# SlaveMCU.net
KiCad netlist of a schematic drawn in EAGLE
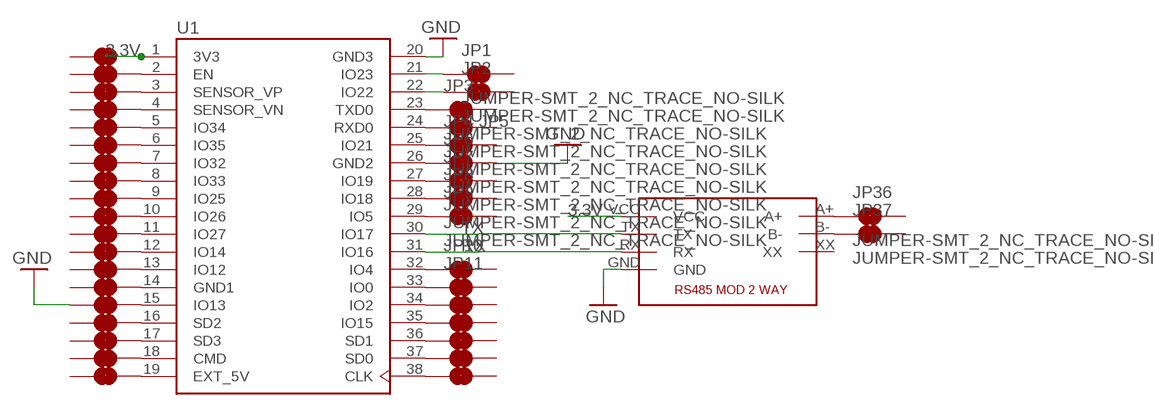
[diagram p0: schematic, sheet 1]

(export (version "E")
  (design (tool "Eeschema 10.0.6"))
  (components
    (comp (ref "JP1")
      (value "JUMPER-SMT_2_NC_TRACE_NO-SILK")
      (footprint "eagle-import:SMT-JUMPER_2_NC_TRACE_NO-SILK")
      (libsource (lib "eagle-import") (part "JUMPER-SMT_2_NC_TRACE_NO-SILK"))
    )
    (comp (ref "JP2")
      (value "JUMPER-SMT_2_NC_TRACE_NO-SILK")
      (footprint "eagle-import:SMT-JUMPER_2_NC_TRACE_NO-SILK")
      (libsource (lib "eagle-import") (part "JUMPER-SMT_2_NC_TRACE_NO-SILK"))
    )
    (comp (ref "JP3")
      (value "JUMPER-SMT_2_NC_TRACE_NO-SILK")
      (footprint "eagle-import:SMT-JUMPER_2_NC_TRACE_NO-SILK")
      (libsource (lib "eagle-import") (part "JUMPER-SMT_2_NC_TRACE_NO-SILK"))
    )
    (comp (ref "JP4")
      (value "JUMPER-SMT_2_NC_TRACE_NO-SILK")
      (footprint "eagle-import:SMT-JUMPER_2_NC_TRACE_NO-SILK")
      (libsource (lib "eagle-import") (part "JUMPER-SMT_2_NC_TRACE_NO-SILK"))
    )
    (comp (ref "JP5")
      (value "JUMPER-SMT_2_NC_TRACE_NO-SILK")
      (footprint "eagle-import:SMT-JUMPER_2_NC_TRACE_NO-SILK")
      (libsource (lib "eagle-import") (part "JUMPER-SMT_2_NC_TRACE_NO-SILK"))
    )
    (comp (ref "JP6")
      (value "JUMPER-SMT_2_NC_TRACE_NO-SILK")
      (footprint "eagle-import:SMT-JUMPER_2_NC_TRACE_NO-SILK")
      (libsource (lib "eagle-import") (part "JUMPER-SMT_2_NC_TRACE_NO-SILK"))
    )
    (comp (ref "JP7")
      (value "JUMPER-SMT_2_NC_TRACE_NO-SILK")
      (footprint "eagle-import:SMT-JUMPER_2_NC_TRACE_NO-SILK")
      (libsource (lib "eagle-import") (part "JUMPER-SMT_2_NC_TRACE_NO-SILK"))
    )
    (comp (ref "JP8")
      (value "JUMPER-SMT_2_NC_TRACE_NO-SILK")
      (footprint "eagle-import:SMT-JUMPER_2_NC_TRACE_NO-SILK")
      (libsource (lib "eagle-import") (part "JUMPER-SMT_2_NC_TRACE_NO-SILK"))
    )
    (comp (ref "JP9")
      (value "JUMPER-SMT_2_NC_TRACE_NO-SILK")
      (footprint "eagle-import:SMT-JUMPER_2_NC_TRACE_NO-SILK")
      (libsource (lib "eagle-import") (part "JUMPER-SMT_2_NC_TRACE_NO-SILK"))
    )
    (comp (ref "JP10")
      (value "JUMPER-SMT_2_NC_TRACE_NO-SILK")
      (footprint "eagle-import:SMT-JUMPER_2_NC_TRACE_NO-SILK")
      (libsource (lib "eagle-import") (part "JUMPER-SMT_2_NC_TRACE_NO-SILK"))
    )
    (comp (ref "JP11")
      (value "JUMPER-SMT_2_NC_TRACE_NO-SILK")
      (footprint "eagle-import:SMT-JUMPER_2_NC_TRACE_NO-SILK")
      (libsource (lib "eagle-import") (part "JUMPER-SMT_2_NC_TRACE_NO-SILK"))
    )
    (comp (ref "JP12")
      (value "JUMPER-SMT_2_NC_TRACE_NO-SILK")
      (footprint "eagle-import:SMT-JUMPER_2_NC_TRACE_NO-SILK")
      (libsource (lib "eagle-import") (part "JUMPER-SMT_2_NC_TRACE_NO-SILK"))
    )
    (comp (ref "JP13")
      (value "JUMPER-SMT_2_NC_TRACE_NO-SILK")
      (footprint "eagle-import:SMT-JUMPER_2_NC_TRACE_NO-SILK")
      (libsource (lib "eagle-import") (part "JUMPER-SMT_2_NC_TRACE_NO-SILK"))
    )
    (comp (ref "JP14")
      (value "JUMPER-SMT_2_NC_TRACE_NO-SILK")
      (footprint "eagle-import:SMT-JUMPER_2_NC_TRACE_NO-SILK")
      (libsource (lib "eagle-import") (part "JUMPER-SMT_2_NC_TRACE_NO-SILK"))
    )
    (comp (ref "JP15")
      (value "JUMPER-SMT_2_NC_TRACE_NO-SILK")
      (footprint "eagle-import:SMT-JUMPER_2_NC_TRACE_NO-SILK")
      (libsource (lib "eagle-import") (part "JUMPER-SMT_2_NC_TRACE_NO-SILK"))
    )
    (comp (ref "JP16")
      (value "JUMPER-SMT_2_NC_TRACE_NO-SILK")
      (footprint "eagle-import:SMT-JUMPER_2_NC_TRACE_NO-SILK")
      (libsource (lib "eagle-import") (part "JUMPER-SMT_2_NC_TRACE_NO-SILK"))
    )
    (comp (ref "JP17")
      (value "JUMPER-SMT_2_NC_TRACE_NO-SILK")
      (footprint "eagle-import:SMT-JUMPER_2_NC_TRACE_NO-SILK")
      (libsource (lib "eagle-import") (part "JUMPER-SMT_2_NC_TRACE_NO-SILK"))
    )
    (comp (ref "JP18")
      (value "JUMPER-SMT_2_NC_TRACE_NO-SILK")
      (footprint "eagle-import:SMT-JUMPER_2_NC_TRACE_NO-SILK")
      (libsource (lib "eagle-import") (part "JUMPER-SMT_2_NC_TRACE_NO-SILK"))
    )
    (comp (ref "JP19")
      (value "JUMPER-SMT_2_NC_TRACE_NO-SILK")
      (footprint "eagle-import:SMT-JUMPER_2_NC_TRACE_NO-SILK")
      (libsource (lib "eagle-import") (part "JUMPER-SMT_2_NC_TRACE_NO-SILK"))
    )
    (comp (ref "JP20")
      (value "JUMPER-SMT_2_NC_TRACE_NO-SILK")
      (footprint "eagle-import:SMT-JUMPER_2_NC_TRACE_NO-SILK")
      (libsource (lib "eagle-import") (part "JUMPER-SMT_2_NC_TRACE_NO-SILK"))
    )
    (comp (ref "JP21")
      (value "JUMPER-SMT_2_NC_TRACE_NO-SILK")
      (footprint "eagle-import:SMT-JUMPER_2_NC_TRACE_NO-SILK")
      (libsource (lib "eagle-import") (part "JUMPER-SMT_2_NC_TRACE_NO-SILK"))
    )
    (comp (ref "JP22")
      (value "JUMPER-SMT_2_NC_TRACE_NO-SILK")
      (footprint "eagle-import:SMT-JUMPER_2_NC_TRACE_NO-SILK")
      (libsource (lib "eagle-import") (part "JUMPER-SMT_2_NC_TRACE_NO-SILK"))
    )
    (comp (ref "JP23")
      (value "JUMPER-SMT_2_NC_TRACE_NO-SILK")
      (footprint "eagle-import:SMT-JUMPER_2_NC_TRACE_NO-SILK")
      (libsource (lib "eagle-import") (part "JUMPER-SMT_2_NC_TRACE_NO-SILK"))
    )
    (comp (ref "JP24")
      (value "JUMPER-SMT_2_NC_TRACE_NO-SILK")
      (footprint "eagle-import:SMT-JUMPER_2_NC_TRACE_NO-SILK")
      (libsource (lib "eagle-import") (part "JUMPER-SMT_2_NC_TRACE_NO-SILK"))
    )
    (comp (ref "JP25")
      (value "JUMPER-SMT_2_NC_TRACE_NO-SILK")
      (footprint "eagle-import:SMT-JUMPER_2_NC_TRACE_NO-SILK")
      (libsource (lib "eagle-import") (part "JUMPER-SMT_2_NC_TRACE_NO-SILK"))
    )
    (comp (ref "JP26")
      (value "JUMPER-SMT_2_NC_TRACE_NO-SILK")
      (footprint "eagle-import:SMT-JUMPER_2_NC_TRACE_NO-SILK")
      (libsource (lib "eagle-import") (part "JUMPER-SMT_2_NC_TRACE_NO-SILK"))
    )
    (comp (ref "JP27")
      (value "JUMPER-SMT_2_NC_TRACE_NO-SILK")
      (footprint "eagle-import:SMT-JUMPER_2_NC_TRACE_NO-SILK")
      (libsource (lib "eagle-import") (part "JUMPER-SMT_2_NC_TRACE_NO-SILK"))
    )
    (comp (ref "JP28")
      (value "JUMPER-SMT_2_NC_TRACE_NO-SILK")
      (footprint "eagle-import:SMT-JUMPER_2_NC_TRACE_NO-SILK")
      (libsource (lib "eagle-import") (part "JUMPER-SMT_2_NC_TRACE_NO-SILK"))
    )
    (comp (ref "JP29")
      (value "JUMPER-SMT_2_NC_TRACE_NO-SILK")
      (footprint "eagle-import:SMT-JUMPER_2_NC_TRACE_NO-SILK")
      (libsource (lib "eagle-import") (part "JUMPER-SMT_2_NC_TRACE_NO-SILK"))
    )
    (comp (ref "JP30")
      (value "JUMPER-SMT_2_NC_TRACE_NO-SILK")
      (footprint "eagle-import:SMT-JUMPER_2_NC_TRACE_NO-SILK")
      (libsource (lib "eagle-import") (part "JUMPER-SMT_2_NC_TRACE_NO-SILK"))
    )
    (comp (ref "JP31")
      (value "JUMPER-SMT_2_NC_TRACE_NO-SILK")
      (footprint "eagle-import:SMT-JUMPER_2_NC_TRACE_NO-SILK")
      (libsource (lib "eagle-import") (part "JUMPER-SMT_2_NC_TRACE_NO-SILK"))
    )
    (comp (ref "JP32")
      (value "JUMPER-SMT_2_NC_TRACE_NO-SILK")
      (footprint "eagle-import:SMT-JUMPER_2_NC_TRACE_NO-SILK")
      (libsource (lib "eagle-import") (part "JUMPER-SMT_2_NC_TRACE_NO-SILK"))
    )
    (comp (ref "JP33")
      (value "JUMPER-SMT_2_NC_TRACE_NO-SILK")
      (footprint "eagle-import:SMT-JUMPER_2_NC_TRACE_NO-SILK")
      (libsource (lib "eagle-import") (part "JUMPER-SMT_2_NC_TRACE_NO-SILK"))
    )
    (comp (ref "JP34")
      (value "JUMPER-SMT_2_NC_TRACE_NO-SILK")
      (footprint "eagle-import:SMT-JUMPER_2_NC_TRACE_NO-SILK")
      (libsource (lib "eagle-import") (part "JUMPER-SMT_2_NC_TRACE_NO-SILK"))
    )
    (comp (ref "JP35")
      (value "JUMPER-SMT_2_NC_TRACE_NO-SILK")
      (footprint "eagle-import:SMT-JUMPER_2_NC_TRACE_NO-SILK")
      (libsource (lib "eagle-import") (part "JUMPER-SMT_2_NC_TRACE_NO-SILK"))
    )
    (comp (ref "JP36")
      (value "JUMPER-SMT_2_NC_TRACE_NO-SILK")
      (footprint "eagle-import:SMT-JUMPER_2_NC_TRACE_NO-SILK")
      (libsource (lib "eagle-import") (part "JUMPER-SMT_2_NC_TRACE_NO-SILK"))
    )
    (comp (ref "JP37")
      (value "JUMPER-SMT_2_NC_TRACE_NO-SILK")
      (footprint "eagle-import:SMT-JUMPER_2_NC_TRACE_NO-SILK")
      (libsource (lib "eagle-import") (part "JUMPER-SMT_2_NC_TRACE_NO-SILK"))
    )
    (comp (ref "U$2")
      (value "RS485_MODULE")
      (footprint "eagle-import:RS485_MODULE")
      (libsource (lib "eagle-import") (part "RS485_MODULE"))
    )
    (comp (ref "U1")
      (value "ESP32-DEVKITC-32D")
      (footprint "eagle-import:MODULE_ESP32-DEVKITC-32D")
      (fields (field (name "MF") "Espressif Systems"))
      (libsource (lib "eagle-import") (part "ESP32-DEVKITC-32D"))
    )
  )
  (nets
    (net (code "1") (name "/3.3V") (class "Default")
      (node (ref "JP35") (pin "2") (pinfunction "2_2") (pintype "passive"))
      (node (ref "U$2") (pin "VCC") (pinfunction "VCC_VCC") (pintype "bidirectional"))
      (node (ref "U1") (pin "1") (pinfunction "3V3_1") (pintype "power_in"))
    )
    (net (code "2") (name "/RX") (class "Default")
      (node (ref "U$2") (pin "RX") (pinfunction "RX_RX") (pintype "bidirectional"))
      (node (ref "U1") (pin "31") (pinfunction "IO16_31") (pintype "bidirectional"))
    )
    (net (code "3") (name "/TX") (class "Default")
      (node (ref "U$2") (pin "TX") (pinfunction "TX_TX") (pintype "bidirectional"))
      (node (ref "U1") (pin "30") (pinfunction "IO17_30") (pintype "bidirectional"))
    )
    (net (code "4") (name "GND") (class "Default")
      (node (ref "JP21") (pin "1") (pinfunction "1_1") (pintype "passive"))
      (node (ref "JP6") (pin "2") (pinfunction "2_2") (pintype "passive"))
      (node (ref "U$2") (pin "GND") (pinfunction "GND_GND") (pintype "bidirectional"))
      (node (ref "U1") (pin "20") (pinfunction "GND3_20") (pintype "power_in"))
    )
    (net (code "5") (name "Net-(JP36-Pad1)") (class "Default")
      (node (ref "JP36") (pin "1") (pinfunction "1_1") (pintype "passive"))
      (node (ref "U$2") (pin "A+") (pinfunction "A+_A+") (pintype "bidirectional"))
    )
    (net (code "6") (name "Net-(JP37-Pad1)") (class "Default")
      (node (ref "JP37") (pin "1") (pinfunction "1_1") (pintype "passive"))
      (node (ref "U$2") (pin "B-") (pinfunction "B-_B-") (pintype "bidirectional"))
    )
    (net (code "7") (name "Net-(U1-CLK)") (class "Default")
      (node (ref "JP16") (pin "1") (pinfunction "1_1") (pintype "passive"))
      (node (ref "U1") (pin "38") (pinfunction "CLK_38") (pintype "input"))
    )
    (net (code "8") (name "Net-(U1-CMD)") (class "Default")
      (node (ref "JP18") (pin "2") (pinfunction "2_2") (pintype "passive"))
      (node (ref "U1") (pin "18") (pinfunction "CMD_18") (pintype "bidirectional"))
    )
    (net (code "9") (name "Net-(U1-EN)") (class "Default")
      (node (ref "JP34") (pin "2") (pinfunction "2_2") (pintype "passive"))
      (node (ref "U1") (pin "2") (pinfunction "EN_2") (pintype "input"))
    )
    (net (code "10") (name "Net-(U1-EXT_5V)") (class "Default")
      (node (ref "JP17") (pin "2") (pinfunction "2_2") (pintype "passive"))
      (node (ref "U1") (pin "19") (pinfunction "EXT_5V_19") (pintype "power_in"))
    )
    (net (code "11") (name "Net-(U1-GND1)") (class "Default")
      (node (ref "JP22") (pin "2") (pinfunction "2_2") (pintype "passive"))
      (node (ref "U1") (pin "14") (pinfunction "GND1_14") (pintype "power_in"))
    )
    (net (code "12") (name "Net-(U1-GND2)") (class "Default")
      (node (ref "JP6") (pin "1") (pinfunction "1_1") (pintype "passive"))
      (node (ref "U1") (pin "26") (pinfunction "GND2_26") (pintype "power_in"))
    )
    (net (code "13") (name "Net-(U1-IO0)") (class "Default")
      (node (ref "JP11") (pin "1") (pinfunction "1_1") (pintype "passive"))
      (node (ref "U1") (pin "33") (pinfunction "IO0_33") (pintype "bidirectional"))
    )
    (net (code "14") (name "Net-(U1-IO2)") (class "Default")
      (node (ref "JP12") (pin "1") (pinfunction "1_1") (pintype "passive"))
      (node (ref "U1") (pin "34") (pinfunction "IO2_34") (pintype "bidirectional"))
    )
    (net (code "15") (name "Net-(U1-IO4)") (class "Default")
      (node (ref "JP10") (pin "1") (pinfunction "1_1") (pintype "passive"))
      (node (ref "U1") (pin "32") (pinfunction "IO4_32") (pintype "bidirectional"))
    )
    (net (code "16") (name "Net-(U1-IO5)") (class "Default")
      (node (ref "JP9") (pin "1") (pinfunction "1_1") (pintype "passive"))
      (node (ref "U1") (pin "29") (pinfunction "IO5_29") (pintype "bidirectional"))
    )
    (net (code "17") (name "Net-(U1-IO12)") (class "Default")
      (node (ref "JP23") (pin "2") (pinfunction "2_2") (pintype "passive"))
      (node (ref "U1") (pin "13") (pinfunction "IO12_13") (pintype "bidirectional"))
    )
    (net (code "18") (name "Net-(U1-IO13)") (class "Default")
      (node (ref "JP21") (pin "2") (pinfunction "2_2") (pintype "passive"))
      (node (ref "U1") (pin "15") (pinfunction "IO13_15") (pintype "bidirectional"))
    )
    (net (code "19") (name "Net-(U1-IO14)") (class "Default")
      (node (ref "JP24") (pin "2") (pinfunction "2_2") (pintype "passive"))
      (node (ref "U1") (pin "12") (pinfunction "IO14_12") (pintype "bidirectional"))
    )
    (net (code "20") (name "Net-(U1-IO15)") (class "Default")
      (node (ref "JP13") (pin "1") (pinfunction "1_1") (pintype "passive"))
      (node (ref "U1") (pin "35") (pinfunction "IO15_35") (pintype "bidirectional"))
    )
    (net (code "21") (name "Net-(U1-IO18)") (class "Default")
      (node (ref "JP8") (pin "1") (pinfunction "1_1") (pintype "passive"))
      (node (ref "U1") (pin "28") (pinfunction "IO18_28") (pintype "bidirectional"))
    )
    (net (code "22") (name "Net-(U1-IO19)") (class "Default")
      (node (ref "JP7") (pin "1") (pinfunction "1_1") (pintype "passive"))
      (node (ref "U1") (pin "27") (pinfunction "IO19_27") (pintype "bidirectional"))
    )
    (net (code "23") (name "Net-(U1-IO21)") (class "Default")
      (node (ref "JP4") (pin "1") (pinfunction "1_1") (pintype "passive"))
      (node (ref "U1") (pin "25") (pinfunction "IO21_25") (pintype "bidirectional"))
    )
    (net (code "24") (name "Net-(U1-IO22)") (class "Default")
      (node (ref "JP2") (pin "1") (pinfunction "1_1") (pintype "passive"))
      (node (ref "U1") (pin "22") (pinfunction "IO22_22") (pintype "bidirectional"))
    )
    (net (code "25") (name "Net-(U1-IO23)") (class "Default")
      (node (ref "JP1") (pin "1") (pinfunction "1_1") (pintype "passive"))
      (node (ref "U1") (pin "21") (pinfunction "IO23_21") (pintype "bidirectional"))
    )
    (net (code "26") (name "Net-(U1-IO25)") (class "Default")
      (node (ref "JP27") (pin "2") (pinfunction "2_2") (pintype "passive"))
      (node (ref "U1") (pin "9") (pinfunction "IO25_9") (pintype "bidirectional"))
    )
    (net (code "27") (name "Net-(U1-IO26)") (class "Default")
      (node (ref "JP26") (pin "2") (pinfunction "2_2") (pintype "passive"))
      (node (ref "U1") (pin "10") (pinfunction "IO26_10") (pintype "bidirectional"))
    )
    (net (code "28") (name "Net-(U1-IO27)") (class "Default")
      (node (ref "JP25") (pin "2") (pinfunction "2_2") (pintype "passive"))
      (node (ref "U1") (pin "11") (pinfunction "IO27_11") (pintype "bidirectional"))
    )
    (net (code "29") (name "Net-(U1-IO32)") (class "Default")
      (node (ref "JP29") (pin "2") (pinfunction "2_2") (pintype "passive"))
      (node (ref "U1") (pin "7") (pinfunction "IO32_7") (pintype "bidirectional"))
    )
    (net (code "30") (name "Net-(U1-IO33)") (class "Default")
      (node (ref "JP28") (pin "2") (pinfunction "2_2") (pintype "passive"))
      (node (ref "U1") (pin "8") (pinfunction "IO33_8") (pintype "bidirectional"))
    )
    (net (code "31") (name "Net-(U1-IO34)") (class "Default")
      (node (ref "JP30") (pin "2") (pinfunction "2_2") (pintype "passive"))
      (node (ref "U1") (pin "5") (pinfunction "IO34_5") (pintype "bidirectional"))
    )
    (net (code "32") (name "Net-(U1-IO35)") (class "Default")
      (node (ref "JP31") (pin "2") (pinfunction "2_2") (pintype "passive"))
      (node (ref "U1") (pin "6") (pinfunction "IO35_6") (pintype "bidirectional"))
    )
    (net (code "33") (name "Net-(U1-RXD0)") (class "Default")
      (node (ref "JP5") (pin "1") (pinfunction "1_1") (pintype "passive"))
      (node (ref "U1") (pin "24") (pinfunction "RXD0_24") (pintype "input"))
    )
    (net (code "34") (name "Net-(U1-SD0)") (class "Default")
      (node (ref "JP15") (pin "1") (pinfunction "1_1") (pintype "passive"))
      (node (ref "U1") (pin "37") (pinfunction "SD0_37") (pintype "bidirectional"))
    )
    (net (code "35") (name "Net-(U1-SD1)") (class "Default")
      (node (ref "JP14") (pin "1") (pinfunction "1_1") (pintype "passive"))
      (node (ref "U1") (pin "36") (pinfunction "SD1_36") (pintype "bidirectional"))
    )
    (net (code "36") (name "Net-(U1-SD2)") (class "Default")
      (node (ref "JP20") (pin "2") (pinfunction "2_2") (pintype "passive"))
      (node (ref "U1") (pin "16") (pinfunction "SD2_16") (pintype "bidirectional"))
    )
    (net (code "37") (name "Net-(U1-SD3)") (class "Default")
      (node (ref "JP19") (pin "2") (pinfunction "2_2") (pintype "passive"))
      (node (ref "U1") (pin "17") (pinfunction "SD3_17") (pintype "bidirectional"))
    )
    (net (code "38") (name "Net-(U1-SENSOR_VN)") (class "Default")
      (node (ref "JP32") (pin "2") (pinfunction "2_2") (pintype "passive"))
      (node (ref "U1") (pin "4") (pinfunction "SENSOR_VN_4") (pintype "input"))
    )
    (net (code "39") (name "Net-(U1-SENSOR_VP)") (class "Default")
      (node (ref "JP33") (pin "2") (pinfunction "2_2") (pintype "passive"))
      (node (ref "U1") (pin "3") (pinfunction "SENSOR_VP_3") (pintype "input"))
    )
    (net (code "40") (name "Net-(U1-TXD0)") (class "Default")
      (node (ref "JP3") (pin "1") (pinfunction "1_1") (pintype "passive"))
      (node (ref "U1") (pin "23") (pinfunction "TXD0_23") (pintype "output"))
    )
    (net (code "41") (name "unconnected-(JP1-Pad2)") (class "Default")
      (node (ref "JP1") (pin "2") (pinfunction "2_2") (pintype "passive"))
    )
    (net (code "42") (name "unconnected-(JP2-Pad2)") (class "Default")
      (node (ref "JP2") (pin "2") (pinfunction "2_2") (pintype "passive"))
    )
    (net (code "43") (name "unconnected-(JP3-Pad2)") (class "Default")
      (node (ref "JP3") (pin "2") (pinfunction "2_2") (pintype "passive"))
    )
    (net (code "44") (name "unconnected-(JP4-Pad2)") (class "Default")
      (node (ref "JP4") (pin "2") (pinfunction "2_2") (pintype "passive"))
    )
    (net (code "45") (name "unconnected-(JP5-Pad2)") (class "Default")
      (node (ref "JP5") (pin "2") (pinfunction "2_2") (pintype "passive"))
    )
    (net (code "46") (name "unconnected-(JP7-Pad2)") (class "Default")
      (node (ref "JP7") (pin "2") (pinfunction "2_2") (pintype "passive"))
    )
    (net (code "47") (name "unconnected-(JP8-Pad2)") (class "Default")
      (node (ref "JP8") (pin "2") (pinfunction "2_2") (pintype "passive"))
    )
    (net (code "48") (name "unconnected-(JP9-Pad2)") (class "Default")
      (node (ref "JP9") (pin "2") (pinfunction "2_2") (pintype "passive"))
    )
    (net (code "49") (name "unconnected-(JP10-Pad2)") (class "Default")
      (node (ref "JP10") (pin "2") (pinfunction "2_2") (pintype "passive"))
    )
    (net (code "50") (name "unconnected-(JP11-Pad2)") (class "Default")
      (node (ref "JP11") (pin "2") (pinfunction "2_2") (pintype "passive"))
    )
    (net (code "51") (name "unconnected-(JP12-Pad2)") (class "Default")
      (node (ref "JP12") (pin "2") (pinfunction "2_2") (pintype "passive"))
    )
    (net (code "52") (name "unconnected-(JP13-Pad2)") (class "Default")
      (node (ref "JP13") (pin "2") (pinfunction "2_2") (pintype "passive"))
    )
    (net (code "53") (name "unconnected-(JP14-Pad2)") (class "Default")
      (node (ref "JP14") (pin "2") (pinfunction "2_2") (pintype "passive"))
    )
    (net (code "54") (name "unconnected-(JP15-Pad2)") (class "Default")
      (node (ref "JP15") (pin "2") (pinfunction "2_2") (pintype "passive"))
    )
    (net (code "55") (name "unconnected-(JP16-Pad2)") (class "Default")
      (node (ref "JP16") (pin "2") (pinfunction "2_2") (pintype "passive"))
    )
    (net (code "56") (name "unconnected-(JP17-Pad1)") (class "Default")
      (node (ref "JP17") (pin "1") (pinfunction "1_1") (pintype "passive"))
    )
    (net (code "57") (name "unconnected-(JP18-Pad1)") (class "Default")
      (node (ref "JP18") (pin "1") (pinfunction "1_1") (pintype "passive"))
    )
    (net (code "58") (name "unconnected-(JP19-Pad1)") (class "Default")
      (node (ref "JP19") (pin "1") (pinfunction "1_1") (pintype "passive"))
    )
    (net (code "59") (name "unconnected-(JP20-Pad1)") (class "Default")
      (node (ref "JP20") (pin "1") (pinfunction "1_1") (pintype "passive"))
    )
    (net (code "60") (name "unconnected-(JP22-Pad1)") (class "Default")
      (node (ref "JP22") (pin "1") (pinfunction "1_1") (pintype "passive"))
    )
    (net (code "61") (name "unconnected-(JP23-Pad1)") (class "Default")
      (node (ref "JP23") (pin "1") (pinfunction "1_1") (pintype "passive"))
    )
    (net (code "62") (name "unconnected-(JP24-Pad1)") (class "Default")
      (node (ref "JP24") (pin "1") (pinfunction "1_1") (pintype "passive"))
    )
    (net (code "63") (name "unconnected-(JP25-Pad1)") (class "Default")
      (node (ref "JP25") (pin "1") (pinfunction "1_1") (pintype "passive"))
    )
    (net (code "64") (name "unconnected-(JP26-Pad1)") (class "Default")
      (node (ref "JP26") (pin "1") (pinfunction "1_1") (pintype "passive"))
    )
    (net (code "65") (name "unconnected-(JP27-Pad1)") (class "Default")
      (node (ref "JP27") (pin "1") (pinfunction "1_1") (pintype "passive"))
    )
    (net (code "66") (name "unconnected-(JP28-Pad1)") (class "Default")
      (node (ref "JP28") (pin "1") (pinfunction "1_1") (pintype "passive"))
    )
    (net (code "67") (name "unconnected-(JP29-Pad1)") (class "Default")
      (node (ref "JP29") (pin "1") (pinfunction "1_1") (pintype "passive"))
    )
    (net (code "68") (name "unconnected-(JP30-Pad1)") (class "Default")
      (node (ref "JP30") (pin "1") (pinfunction "1_1") (pintype "passive"))
    )
    (net (code "69") (name "unconnected-(JP31-Pad1)") (class "Default")
      (node (ref "JP31") (pin "1") (pinfunction "1_1") (pintype "passive"))
    )
    (net (code "70") (name "unconnected-(JP32-Pad1)") (class "Default")
      (node (ref "JP32") (pin "1") (pinfunction "1_1") (pintype "passive"))
    )
    (net (code "71") (name "unconnected-(JP33-Pad1)") (class "Default")
      (node (ref "JP33") (pin "1") (pinfunction "1_1") (pintype "passive"))
    )
    (net (code "72") (name "unconnected-(JP34-Pad1)") (class "Default")
      (node (ref "JP34") (pin "1") (pinfunction "1_1") (pintype "passive"))
    )
    (net (code "73") (name "unconnected-(JP35-Pad1)") (class "Default")
      (node (ref "JP35") (pin "1") (pinfunction "1_1") (pintype "passive"))
    )
    (net (code "74") (name "unconnected-(JP36-Pad2)") (class "Default")
      (node (ref "JP36") (pin "2") (pinfunction "2_2") (pintype "passive"))
    )
    (net (code "75") (name "unconnected-(JP37-Pad2)") (class "Default")
      (node (ref "JP37") (pin "2") (pinfunction "2_2") (pintype "passive"))
    )
    (net (code "76") (name "unconnected-(U$2-PadXX)") (class "Default")
      (node (ref "U$2") (pin "XX") (pinfunction "XX_XX") (pintype "bidirectional"))
    )
  )
)
